# project2.net
KiCad netlist of a schematic drawn in EAGLE
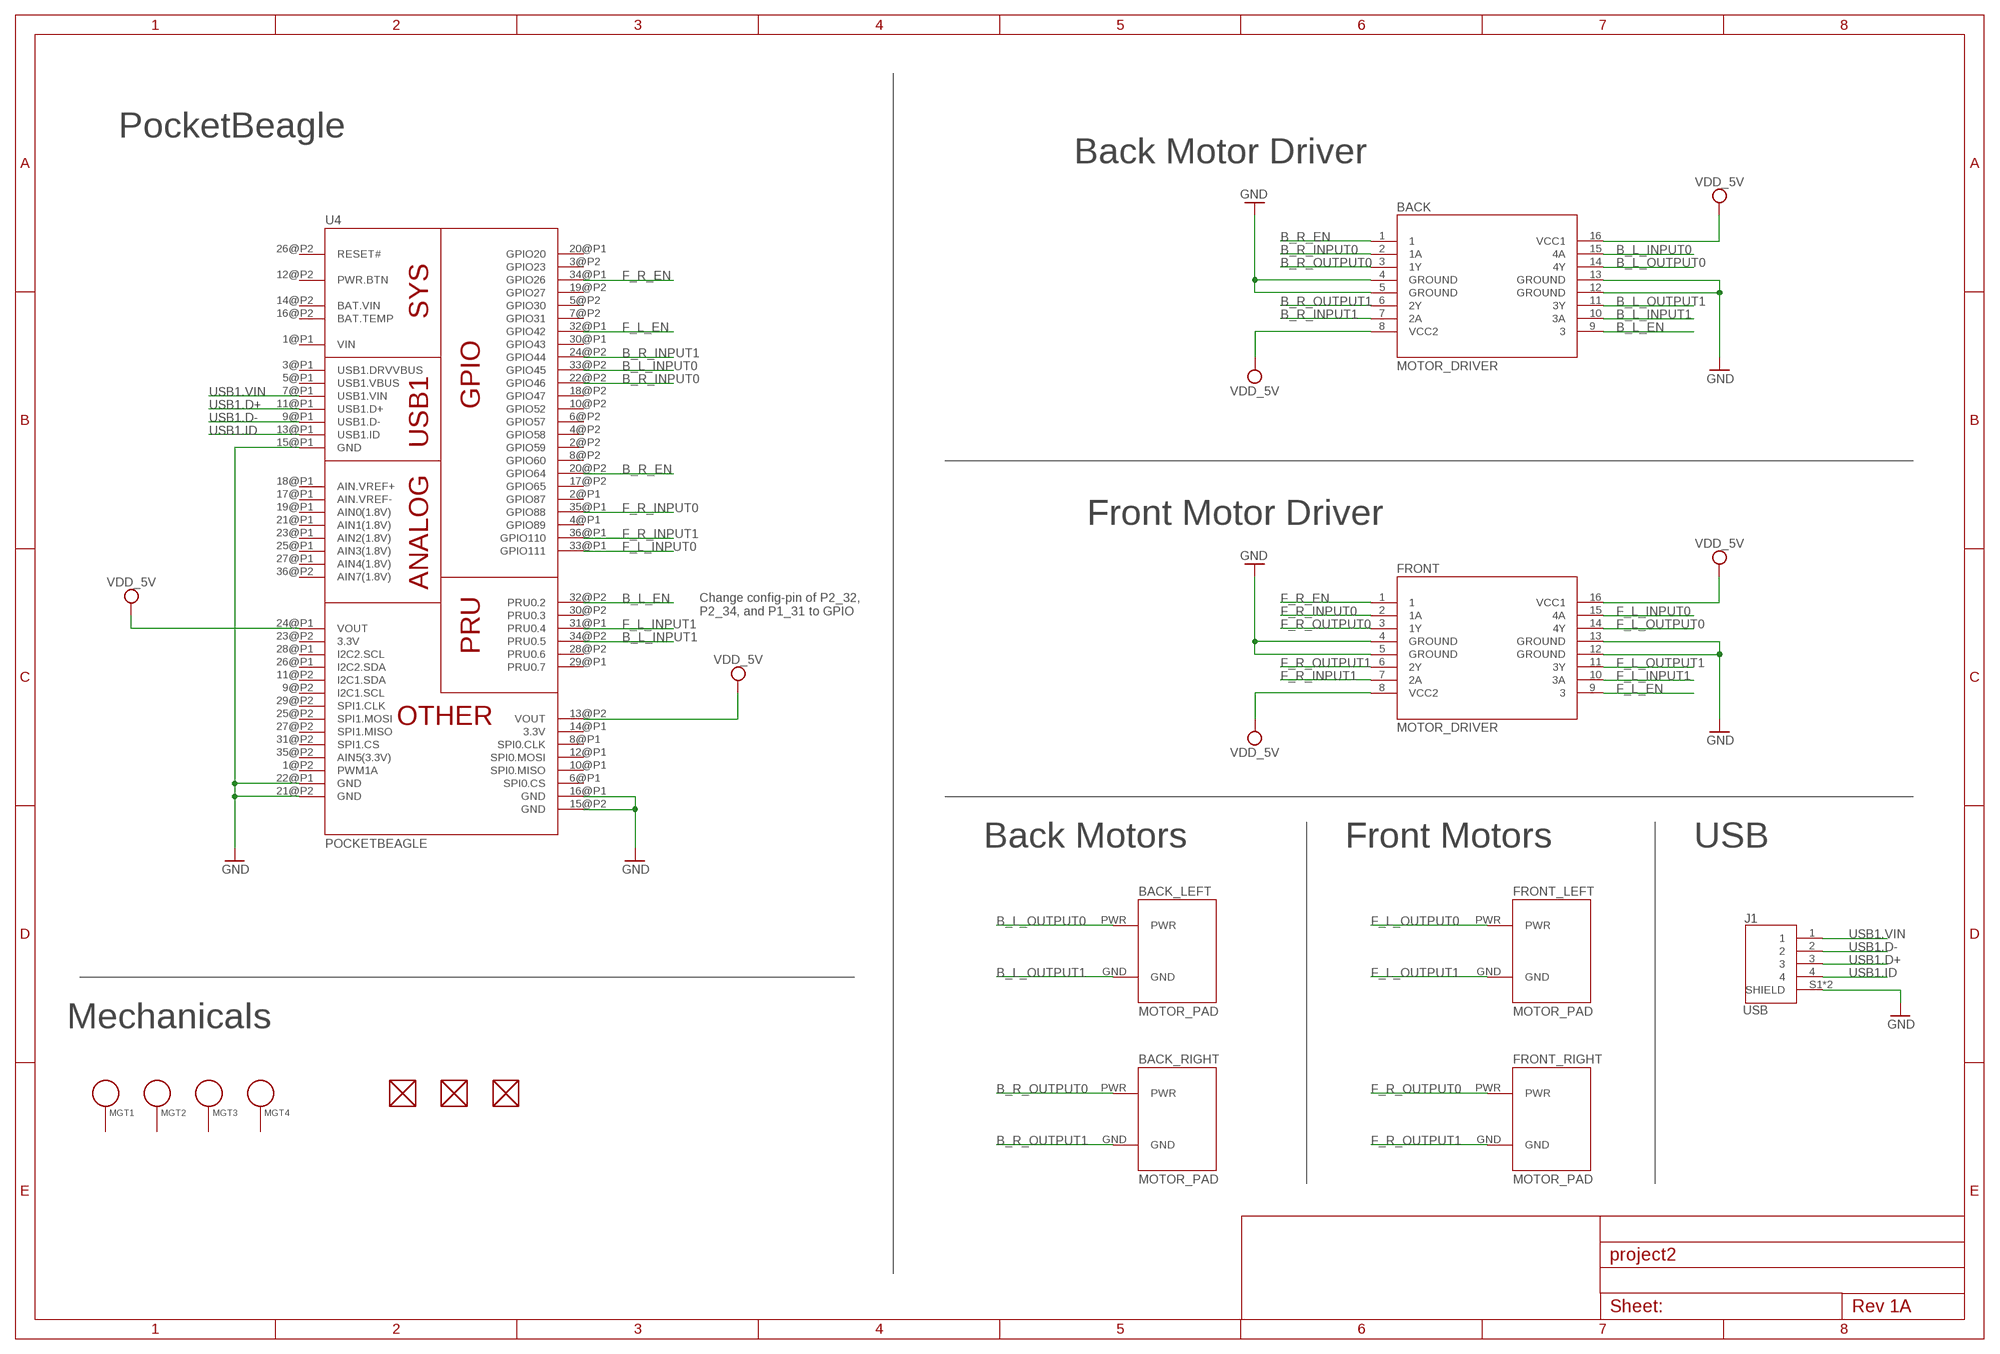
[diagram p0: schematic, sheet 1]

(export (version "E")
  (design (tool "Eeschema 10.0.6"))
  (components
    (comp (ref "BACK")
      (value "MOTOR_DRIVER")
      (footprint "eagle-import:MOTOR_DRIVER")
      (fields (field (name "GENERIC_PART_NUMBER") "L293D") (field (name "MANUFACTURER") "Texas Instruments"))
      (libsource (lib "eagle-import") (part "MOTOR_DRIVER"))
    )
    (comp (ref "BACK_LEFT")
      (value "MOTOR_PAD")
      (footprint "eagle-import:MOTOR_PAD")
      (libsource (lib "eagle-import") (part "MOTOR_PAD"))
    )
    (comp (ref "BACK_RIGHT")
      (value "MOTOR_PAD")
      (footprint "eagle-import:MOTOR_PAD")
      (libsource (lib "eagle-import") (part "MOTOR_PAD"))
    )
    (comp (ref "FRONT")
      (value "MOTOR_DRIVER")
      (footprint "eagle-import:MOTOR_DRIVER")
      (fields (field (name "GENERIC_PART_NUMBER") "L293D") (field (name "MANUFACTURER") "Texas Instruments"))
      (libsource (lib "eagle-import") (part "MOTOR_DRIVER"))
    )
    (comp (ref "FRONT_LEFT")
      (value "MOTOR_PAD")
      (footprint "eagle-import:MOTOR_PAD")
      (libsource (lib "eagle-import") (part "MOTOR_PAD"))
    )
    (comp (ref "FRONT_RIGHT")
      (value "MOTOR_PAD")
      (footprint "eagle-import:MOTOR_PAD")
      (libsource (lib "eagle-import") (part "MOTOR_PAD"))
    )
    (comp (ref "FUD1")
      (value "FIDUCIAL")
      (footprint "eagle-import:FIDUCIAL_40MIL")
      (libsource (lib "eagle-import") (part "FIDUCIAL"))
    )
    (comp (ref "FUD2")
      (value "FIDUCIAL")
      (footprint "eagle-import:FIDUCIAL_40MIL")
      (libsource (lib "eagle-import") (part "FIDUCIAL"))
    )
    (comp (ref "FUD3")
      (value "FIDUCIAL")
      (footprint "eagle-import:FIDUCIAL_40MIL")
      (libsource (lib "eagle-import") (part "FIDUCIAL"))
    )
    (comp (ref "J1")
      (value "USB")
      (footprint "eagle-import:J_SMD_292303-9-4_2,2.5_14.85_14.06_8.9")
      (fields (field (name "COMMENT") "292303-9") (field (name "MF") "TE Connectivity"))
      (libsource (lib "eagle-import") (part "USB"))
    )
    (comp (ref "MGT1")
      (value "MOUNTING_HOLE")
      (footprint "eagle-import:MOUNTING_HOLE")
      (libsource (lib "eagle-import") (part "MOUNTING_HOLE"))
    )
    (comp (ref "MGT2")
      (value "MOUNTING_HOLE")
      (footprint "eagle-import:MOUNTING_HOLE")
      (libsource (lib "eagle-import") (part "MOUNTING_HOLE"))
    )
    (comp (ref "MGT3")
      (value "MOUNTING_HOLE")
      (footprint "eagle-import:MOUNTING_HOLE")
      (libsource (lib "eagle-import") (part "MOUNTING_HOLE"))
    )
    (comp (ref "MGT4")
      (value "MOUNTING_HOLE")
      (footprint "eagle-import:MOUNTING_HOLE")
      (libsource (lib "eagle-import") (part "MOUNTING_HOLE"))
    )
    (comp (ref "U4")
      (value "POCKETBEAGLE")
      (footprint "eagle-import:POCKETBEAGLE")
      (libsource (lib "eagle-import") (part "POCKETBEAGLE"))
    )
  )
  (nets
    (net (code "1") (name "/BAT.VIN") (class "Default")
      (node (ref "U4") (pin "14@P2") (pinfunction "BAT.VIN_14@P2") (pintype "power_in"))
    )
    (net (code "2") (name "/B_L_EN") (class "Default")
      (node (ref "BACK") (pin "9") (pinfunction "3_9") (pintype "passive"))
      (node (ref "U4") (pin "32@P2") (pinfunction "PRU0.2_32@P2") (pintype "bidirectional"))
    )
    (net (code "3") (name "/B_L_INPUT0") (class "Default")
      (node (ref "BACK") (pin "15") (pinfunction "4A_15") (pintype "input"))
      (node (ref "U4") (pin "33@P2") (pinfunction "GPIO45_33@P2") (pintype "bidirectional"))
    )
    (net (code "4") (name "/B_L_INPUT1") (class "Default")
      (node (ref "BACK") (pin "10") (pinfunction "3A_10") (pintype "input"))
      (node (ref "U4") (pin "34@P2") (pinfunction "PRU0.5_34@P2") (pintype "bidirectional"))
    )
    (net (code "5") (name "/B_L_OUTPUT0") (class "Default")
      (node (ref "BACK") (pin "14") (pinfunction "4Y_14") (pintype "output"))
      (node (ref "BACK_LEFT") (pin "PWR") (pinfunction "PWR_PWR") (pintype "bidirectional"))
    )
    (net (code "6") (name "/B_L_OUTPUT1") (class "Default")
      (node (ref "BACK") (pin "11") (pinfunction "3Y_11") (pintype "output"))
      (node (ref "BACK_LEFT") (pin "GND") (pinfunction "GND_GND") (pintype "bidirectional"))
    )
    (net (code "7") (name "/B_R_EN") (class "Default")
      (node (ref "BACK") (pin "1") (pinfunction "1_1") (pintype "passive"))
      (node (ref "U4") (pin "20@P2") (pinfunction "GPIO64_20@P2") (pintype "bidirectional"))
    )
    (net (code "8") (name "/B_R_INPUT0") (class "Default")
      (node (ref "BACK") (pin "2") (pinfunction "1A_2") (pintype "input"))
      (node (ref "U4") (pin "22@P2") (pinfunction "GPIO46_22@P2") (pintype "bidirectional"))
    )
    (net (code "9") (name "/B_R_INPUT1") (class "Default")
      (node (ref "BACK") (pin "7") (pinfunction "2A_7") (pintype "input"))
      (node (ref "U4") (pin "24@P2") (pinfunction "GPIO44_24@P2") (pintype "bidirectional"))
    )
    (net (code "10") (name "/B_R_OUTPUT0") (class "Default")
      (node (ref "BACK") (pin "3") (pinfunction "1Y_3") (pintype "output"))
      (node (ref "BACK_RIGHT") (pin "PWR") (pinfunction "PWR_PWR") (pintype "bidirectional"))
    )
    (net (code "11") (name "/B_R_OUTPUT1") (class "Default")
      (node (ref "BACK") (pin "6") (pinfunction "2Y_6") (pintype "output"))
      (node (ref "BACK_RIGHT") (pin "GND") (pinfunction "GND_GND") (pintype "bidirectional"))
    )
    (net (code "12") (name "/F_L_EN") (class "Default")
      (node (ref "FRONT") (pin "9") (pinfunction "3_9") (pintype "passive"))
      (node (ref "U4") (pin "32@P1") (pinfunction "GPIO42_32@P1") (pintype "bidirectional"))
    )
    (net (code "13") (name "/F_L_INPUT0") (class "Default")
      (node (ref "FRONT") (pin "15") (pinfunction "4A_15") (pintype "input"))
      (node (ref "U4") (pin "33@P1") (pinfunction "GPIO111_33@P1") (pintype "bidirectional"))
    )
    (net (code "14") (name "/F_L_INPUT1") (class "Default")
      (node (ref "FRONT") (pin "10") (pinfunction "3A_10") (pintype "input"))
      (node (ref "U4") (pin "31@P1") (pinfunction "PRU0.4_31@P1") (pintype "bidirectional"))
    )
    (net (code "15") (name "/F_L_OUTPUT0") (class "Default")
      (node (ref "FRONT") (pin "14") (pinfunction "4Y_14") (pintype "output"))
      (node (ref "FRONT_LEFT") (pin "PWR") (pinfunction "PWR_PWR") (pintype "bidirectional"))
    )
    (net (code "16") (name "/F_L_OUTPUT1") (class "Default")
      (node (ref "FRONT") (pin "11") (pinfunction "3Y_11") (pintype "output"))
      (node (ref "FRONT_LEFT") (pin "GND") (pinfunction "GND_GND") (pintype "bidirectional"))
    )
    (net (code "17") (name "/F_R_EN") (class "Default")
      (node (ref "FRONT") (pin "1") (pinfunction "1_1") (pintype "passive"))
      (node (ref "U4") (pin "34@P1") (pinfunction "GPIO26_34@P1") (pintype "bidirectional"))
    )
    (net (code "18") (name "/F_R_INPUT0") (class "Default")
      (node (ref "FRONT") (pin "2") (pinfunction "1A_2") (pintype "input"))
      (node (ref "U4") (pin "35@P1") (pinfunction "GPIO88_35@P1") (pintype "bidirectional"))
    )
    (net (code "19") (name "/F_R_INPUT1") (class "Default")
      (node (ref "FRONT") (pin "7") (pinfunction "2A_7") (pintype "input"))
      (node (ref "U4") (pin "36@P1") (pinfunction "GPIO110_36@P1") (pintype "bidirectional"))
    )
    (net (code "20") (name "/F_R_OUTPUT0") (class "Default")
      (node (ref "FRONT") (pin "3") (pinfunction "1Y_3") (pintype "output"))
      (node (ref "FRONT_RIGHT") (pin "PWR") (pinfunction "PWR_PWR") (pintype "bidirectional"))
    )
    (net (code "21") (name "/F_R_OUTPUT1") (class "Default")
      (node (ref "FRONT") (pin "6") (pinfunction "2Y_6") (pintype "output"))
      (node (ref "FRONT_RIGHT") (pin "GND") (pinfunction "GND_GND") (pintype "bidirectional"))
    )
    (net (code "22") (name "/USB1.D+") (class "Default")
      (node (ref "J1") (pin "3") (pinfunction "3_3") (pintype "passive"))
      (node (ref "U4") (pin "11@P1") (pinfunction "USB1.D+_11@P1") (pintype "bidirectional"))
    )
    (net (code "23") (name "/USB1.D-") (class "Default")
      (node (ref "J1") (pin "2") (pinfunction "2_2") (pintype "passive"))
      (node (ref "U4") (pin "9@P1") (pinfunction "USB1.D-_9@P1") (pintype "bidirectional"))
    )
    (net (code "24") (name "/USB1.ID") (class "Default")
      (node (ref "J1") (pin "4") (pinfunction "4_4") (pintype "passive"))
      (node (ref "U4") (pin "13@P1") (pinfunction "USB1.ID_13@P1") (pintype "bidirectional"))
    )
    (net (code "25") (name "/USB1.VIN") (class "Default")
      (node (ref "J1") (pin "1") (pinfunction "1_1") (pintype "passive"))
      (node (ref "U4") (pin "7@P1") (pinfunction "USB1.VIN_7@P1") (pintype "bidirectional"))
    )
    (net (code "26") (name "/VIN") (class "Default")
      (node (ref "U4") (pin "1@P1") (pinfunction "VIN_1@P1") (pintype "power_in"))
    )
    (net (code "27") (name "GND") (class "Default")
      (node (ref "BACK") (pin "12") (pinfunction "GROUND_12") (pintype "passive"))
      (node (ref "BACK") (pin "13") (pinfunction "GROUND_13") (pintype "passive"))
      (node (ref "BACK") (pin "4") (pinfunction "GROUND_4") (pintype "passive"))
      (node (ref "BACK") (pin "5") (pinfunction "GROUND_5") (pintype "passive"))
      (node (ref "FRONT") (pin "12") (pinfunction "GROUND_12") (pintype "passive"))
      (node (ref "FRONT") (pin "13") (pinfunction "GROUND_13") (pintype "passive"))
      (node (ref "FRONT") (pin "4") (pinfunction "GROUND_4") (pintype "passive"))
      (node (ref "FRONT") (pin "5") (pinfunction "GROUND_5") (pintype "passive"))
      (node (ref "J1") (pin "S1") (pinfunction "SHIELD_S1") (pintype "passive"))
      (node (ref "J1") (pin "S2") (pinfunction "SHIELD_S2") (pintype "passive"))
      (node (ref "U4") (pin "15@P1") (pinfunction "GND_15@P1") (pintype "bidirectional"))
      (node (ref "U4") (pin "15@P2") (pinfunction "GND_15@P2") (pintype "power_in"))
      (node (ref "U4") (pin "16@P1") (pinfunction "GND_16@P1") (pintype "power_in"))
      (node (ref "U4") (pin "21@P2") (pinfunction "GND_21@P2") (pintype "power_in"))
      (node (ref "U4") (pin "22@P1") (pinfunction "GND_22@P1") (pintype "power_in"))
    )
    (net (code "28") (name "VDD_5V") (class "Default")
      (node (ref "BACK") (pin "16") (pinfunction "VCC1_16") (pintype "power_in"))
      (node (ref "BACK") (pin "8") (pinfunction "VCC2_8") (pintype "power_in"))
      (node (ref "FRONT") (pin "16") (pinfunction "VCC1_16") (pintype "power_in"))
      (node (ref "FRONT") (pin "8") (pinfunction "VCC2_8") (pintype "power_in"))
      (node (ref "U4") (pin "13@P2") (pinfunction "VOUT_13@P2") (pintype "power_in"))
      (node (ref "U4") (pin "24@P1") (pinfunction "VOUT_24@P1") (pintype "power_in"))
    )
    (net (code "29") (name "unconnected-(FUD1-PadP$1)") (class "Default")
      (node (ref "FUD1") (pin "P$1") (pinfunction "P$1_P$1") (pintype "no_connect"))
    )
    (net (code "30") (name "unconnected-(FUD2-PadP$1)") (class "Default")
      (node (ref "FUD2") (pin "P$1") (pinfunction "P$1_P$1") (pintype "no_connect"))
    )
    (net (code "31") (name "unconnected-(FUD3-PadP$1)") (class "Default")
      (node (ref "FUD3") (pin "P$1") (pinfunction "P$1_P$1") (pintype "no_connect"))
    )
    (net (code "32") (name "unconnected-(MGT1-PadP$1)") (class "Default")
      (node (ref "MGT1") (pin "P$1") (pinfunction "P$1_P$1") (pintype "bidirectional"))
    )
    (net (code "33") (name "unconnected-(MGT2-PadP$1)") (class "Default")
      (node (ref "MGT2") (pin "P$1") (pinfunction "P$1_P$1") (pintype "bidirectional"))
    )
    (net (code "34") (name "unconnected-(MGT3-PadP$1)") (class "Default")
      (node (ref "MGT3") (pin "P$1") (pinfunction "P$1_P$1") (pintype "bidirectional"))
    )
    (net (code "35") (name "unconnected-(MGT4-PadP$1)") (class "Default")
      (node (ref "MGT4") (pin "P$1") (pinfunction "P$1_P$1") (pintype "bidirectional"))
    )
    (net (code "36") (name "unconnected-(U4-3.3V-Pad14@P1)") (class "Default")
      (node (ref "U4") (pin "14@P1") (pinfunction "3.3V_14@P1") (pintype "bidirectional"))
    )
    (net (code "37") (name "unconnected-(U4-3.3V-Pad23@P2)") (class "Default")
      (node (ref "U4") (pin "23@P2") (pinfunction "3.3V_23@P2") (pintype "bidirectional"))
    )
    (net (code "38") (name "unconnected-(U4-AIN.VREF+-Pad18@P1)") (class "Default")
      (node (ref "U4") (pin "18@P1") (pinfunction "AIN.VREF+_18@P1") (pintype "bidirectional"))
    )
    (net (code "39") (name "unconnected-(U4-AIN.VREF--Pad17@P1)") (class "Default")
      (node (ref "U4") (pin "17@P1") (pinfunction "AIN.VREF-_17@P1") (pintype "bidirectional"))
    )
    (net (code "40") (name "unconnected-(U4-AIN0(1.8V)-Pad19@P1)") (class "Default")
      (node (ref "U4") (pin "19@P1") (pinfunction "AIN0(1.8V)_19@P1") (pintype "bidirectional"))
    )
    (net (code "41") (name "unconnected-(U4-AIN1(1.8V)-Pad21@P1)") (class "Default")
      (node (ref "U4") (pin "21@P1") (pinfunction "AIN1(1.8V)_21@P1") (pintype "bidirectional"))
    )
    (net (code "42") (name "unconnected-(U4-AIN2(1.8V)-Pad23@P1)") (class "Default")
      (node (ref "U4") (pin "23@P1") (pinfunction "AIN2(1.8V)_23@P1") (pintype "bidirectional"))
    )
    (net (code "43") (name "unconnected-(U4-AIN3(1.8V)-Pad25@P1)") (class "Default")
      (node (ref "U4") (pin "25@P1") (pinfunction "AIN3(1.8V)_25@P1") (pintype "bidirectional"))
    )
    (net (code "44") (name "unconnected-(U4-AIN4(1.8V)-Pad27@P1)") (class "Default")
      (node (ref "U4") (pin "27@P1") (pinfunction "AIN4(1.8V)_27@P1") (pintype "bidirectional"))
    )
    (net (code "45") (name "unconnected-(U4-AIN5(3.3V)-Pad35@P2)") (class "Default")
      (node (ref "U4") (pin "35@P2") (pinfunction "AIN5(3.3V)_35@P2") (pintype "bidirectional"))
    )
    (net (code "46") (name "unconnected-(U4-AIN7(1.8V)-Pad36@P2)") (class "Default")
      (node (ref "U4") (pin "36@P2") (pinfunction "AIN7(1.8V)_36@P2") (pintype "bidirectional"))
    )
    (net (code "47") (name "unconnected-(U4-BAT.TEMP-Pad16@P2)") (class "Default")
      (node (ref "U4") (pin "16@P2") (pinfunction "BAT.TEMP_16@P2") (pintype "bidirectional"))
    )
    (net (code "48") (name "unconnected-(U4-GPIO20-Pad20@P1)") (class "Default")
      (node (ref "U4") (pin "20@P1") (pinfunction "GPIO20_20@P1") (pintype "bidirectional"))
    )
    (net (code "49") (name "unconnected-(U4-GPIO23-Pad3@P2)") (class "Default")
      (node (ref "U4") (pin "3@P2") (pinfunction "GPIO23_3@P2") (pintype "bidirectional"))
    )
    (net (code "50") (name "unconnected-(U4-GPIO27-Pad19@P2)") (class "Default")
      (node (ref "U4") (pin "19@P2") (pinfunction "GPIO27_19@P2") (pintype "bidirectional"))
    )
    (net (code "51") (name "unconnected-(U4-GPIO30-Pad5@P2)") (class "Default")
      (node (ref "U4") (pin "5@P2") (pinfunction "GPIO30_5@P2") (pintype "bidirectional"))
    )
    (net (code "52") (name "unconnected-(U4-GPIO31-Pad7@P2)") (class "Default")
      (node (ref "U4") (pin "7@P2") (pinfunction "GPIO31_7@P2") (pintype "bidirectional"))
    )
    (net (code "53") (name "unconnected-(U4-GPIO43-Pad30@P1)") (class "Default")
      (node (ref "U4") (pin "30@P1") (pinfunction "GPIO43_30@P1") (pintype "bidirectional"))
    )
    (net (code "54") (name "unconnected-(U4-GPIO47-Pad18@P2)") (class "Default")
      (node (ref "U4") (pin "18@P2") (pinfunction "GPIO47_18@P2") (pintype "bidirectional"))
    )
    (net (code "55") (name "unconnected-(U4-GPIO52-Pad10@P2)") (class "Default")
      (node (ref "U4") (pin "10@P2") (pinfunction "GPIO52_10@P2") (pintype "bidirectional"))
    )
    (net (code "56") (name "unconnected-(U4-GPIO57-Pad6@P2)") (class "Default")
      (node (ref "U4") (pin "6@P2") (pinfunction "GPIO57_6@P2") (pintype "bidirectional"))
    )
    (net (code "57") (name "unconnected-(U4-GPIO58-Pad4@P2)") (class "Default")
      (node (ref "U4") (pin "4@P2") (pinfunction "GPIO58_4@P2") (pintype "bidirectional"))
    )
    (net (code "58") (name "unconnected-(U4-GPIO59-Pad2@P2)") (class "Default")
      (node (ref "U4") (pin "2@P2") (pinfunction "GPIO59_2@P2") (pintype "bidirectional"))
    )
    (net (code "59") (name "unconnected-(U4-GPIO60-Pad8@P2)") (class "Default")
      (node (ref "U4") (pin "8@P2") (pinfunction "GPIO60_8@P2") (pintype "bidirectional"))
    )
    (net (code "60") (name "unconnected-(U4-GPIO65-Pad17@P2)") (class "Default")
      (node (ref "U4") (pin "17@P2") (pinfunction "GPIO65_17@P2") (pintype "bidirectional"))
    )
    (net (code "61") (name "unconnected-(U4-GPIO87-Pad2@P1)") (class "Default")
      (node (ref "U4") (pin "2@P1") (pinfunction "GPIO87_2@P1") (pintype "bidirectional"))
    )
    (net (code "62") (name "unconnected-(U4-GPIO89-Pad4@P1)") (class "Default")
      (node (ref "U4") (pin "4@P1") (pinfunction "GPIO89_4@P1") (pintype "bidirectional"))
    )
    (net (code "63") (name "unconnected-(U4-I2C1.SCL-Pad9@P2)") (class "Default")
      (node (ref "U4") (pin "9@P2") (pinfunction "I2C1.SCL_9@P2") (pintype "bidirectional"))
    )
    (net (code "64") (name "unconnected-(U4-I2C1.SDA-Pad11@P2)") (class "Default")
      (node (ref "U4") (pin "11@P2") (pinfunction "I2C1.SDA_11@P2") (pintype "bidirectional"))
    )
    (net (code "65") (name "unconnected-(U4-I2C2.SCL-Pad28@P1)") (class "Default")
      (node (ref "U4") (pin "28@P1") (pinfunction "I2C2.SCL_28@P1") (pintype "bidirectional"))
    )
    (net (code "66") (name "unconnected-(U4-I2C2.SDA-Pad26@P1)") (class "Default")
      (node (ref "U4") (pin "26@P1") (pinfunction "I2C2.SDA_26@P1") (pintype "bidirectional"))
    )
    (net (code "67") (name "unconnected-(U4-PRU0.3-Pad30@P2)") (class "Default")
      (node (ref "U4") (pin "30@P2") (pinfunction "PRU0.3_30@P2") (pintype "bidirectional"))
    )
    (net (code "68") (name "unconnected-(U4-PRU0.6-Pad28@P2)") (class "Default")
      (node (ref "U4") (pin "28@P2") (pinfunction "PRU0.6_28@P2") (pintype "bidirectional"))
    )
    (net (code "69") (name "unconnected-(U4-PRU0.7-Pad29@P1)") (class "Default")
      (node (ref "U4") (pin "29@P1") (pinfunction "PRU0.7_29@P1") (pintype "bidirectional"))
    )
    (net (code "70") (name "unconnected-(U4-PWM1A-Pad1@P2)") (class "Default")
      (node (ref "U4") (pin "1@P2") (pinfunction "PWM1A_1@P2") (pintype "bidirectional"))
    )
    (net (code "71") (name "unconnected-(U4-PWR.BTN-Pad12@P2)") (class "Default")
      (node (ref "U4") (pin "12@P2") (pinfunction "PWR.BTN_12@P2") (pintype "bidirectional"))
    )
    (net (code "72") (name "unconnected-(U4-RESET#-Pad26@P2)") (class "Default")
      (node (ref "U4") (pin "26@P2") (pinfunction "RESET#_26@P2") (pintype "bidirectional"))
    )
    (net (code "73") (name "unconnected-(U4-SPI0.CLK-Pad8@P1)") (class "Default")
      (node (ref "U4") (pin "8@P1") (pinfunction "SPI0.CLK_8@P1") (pintype "bidirectional"))
    )
    (net (code "74") (name "unconnected-(U4-SPI0.CS-Pad6@P1)") (class "Default")
      (node (ref "U4") (pin "6@P1") (pinfunction "SPI0.CS_6@P1") (pintype "bidirectional"))
    )
    (net (code "75") (name "unconnected-(U4-SPI0.MISO-Pad10@P1)") (class "Default")
      (node (ref "U4") (pin "10@P1") (pinfunction "SPI0.MISO_10@P1") (pintype "bidirectional"))
    )
    (net (code "76") (name "unconnected-(U4-SPI0.MOSI-Pad12@P1)") (class "Default")
      (node (ref "U4") (pin "12@P1") (pinfunction "SPI0.MOSI_12@P1") (pintype "bidirectional"))
    )
    (net (code "77") (name "unconnected-(U4-SPI1.CLK-Pad29@P2)") (class "Default")
      (node (ref "U4") (pin "29@P2") (pinfunction "SPI1.CLK_29@P2") (pintype "bidirectional"))
    )
    (net (code "78") (name "unconnected-(U4-SPI1.CS-Pad31@P2)") (class "Default")
      (node (ref "U4") (pin "31@P2") (pinfunction "SPI1.CS_31@P2") (pintype "bidirectional"))
    )
    (net (code "79") (name "unconnected-(U4-SPI1.MISO-Pad27@P2)") (class "Default")
      (node (ref "U4") (pin "27@P2") (pinfunction "SPI1.MISO_27@P2") (pintype "bidirectional"))
    )
    (net (code "80") (name "unconnected-(U4-SPI1.MOSI-Pad25@P2)") (class "Default")
      (node (ref "U4") (pin "25@P2") (pinfunction "SPI1.MOSI_25@P2") (pintype "bidirectional"))
    )
    (net (code "81") (name "unconnected-(U4-USB1.DRVVBUS-Pad3@P1)") (class "Default")
      (node (ref "U4") (pin "3@P1") (pinfunction "USB1.DRVVBUS_3@P1") (pintype "bidirectional"))
    )
    (net (code "82") (name "unconnected-(U4-USB1.VBUS-Pad5@P1)") (class "Default")
      (node (ref "U4") (pin "5@P1") (pinfunction "USB1.VBUS_5@P1") (pintype "bidirectional"))
    )
  )
)
